# RS485.net
KiCad netlist of a schematic drawn in Altium Designer
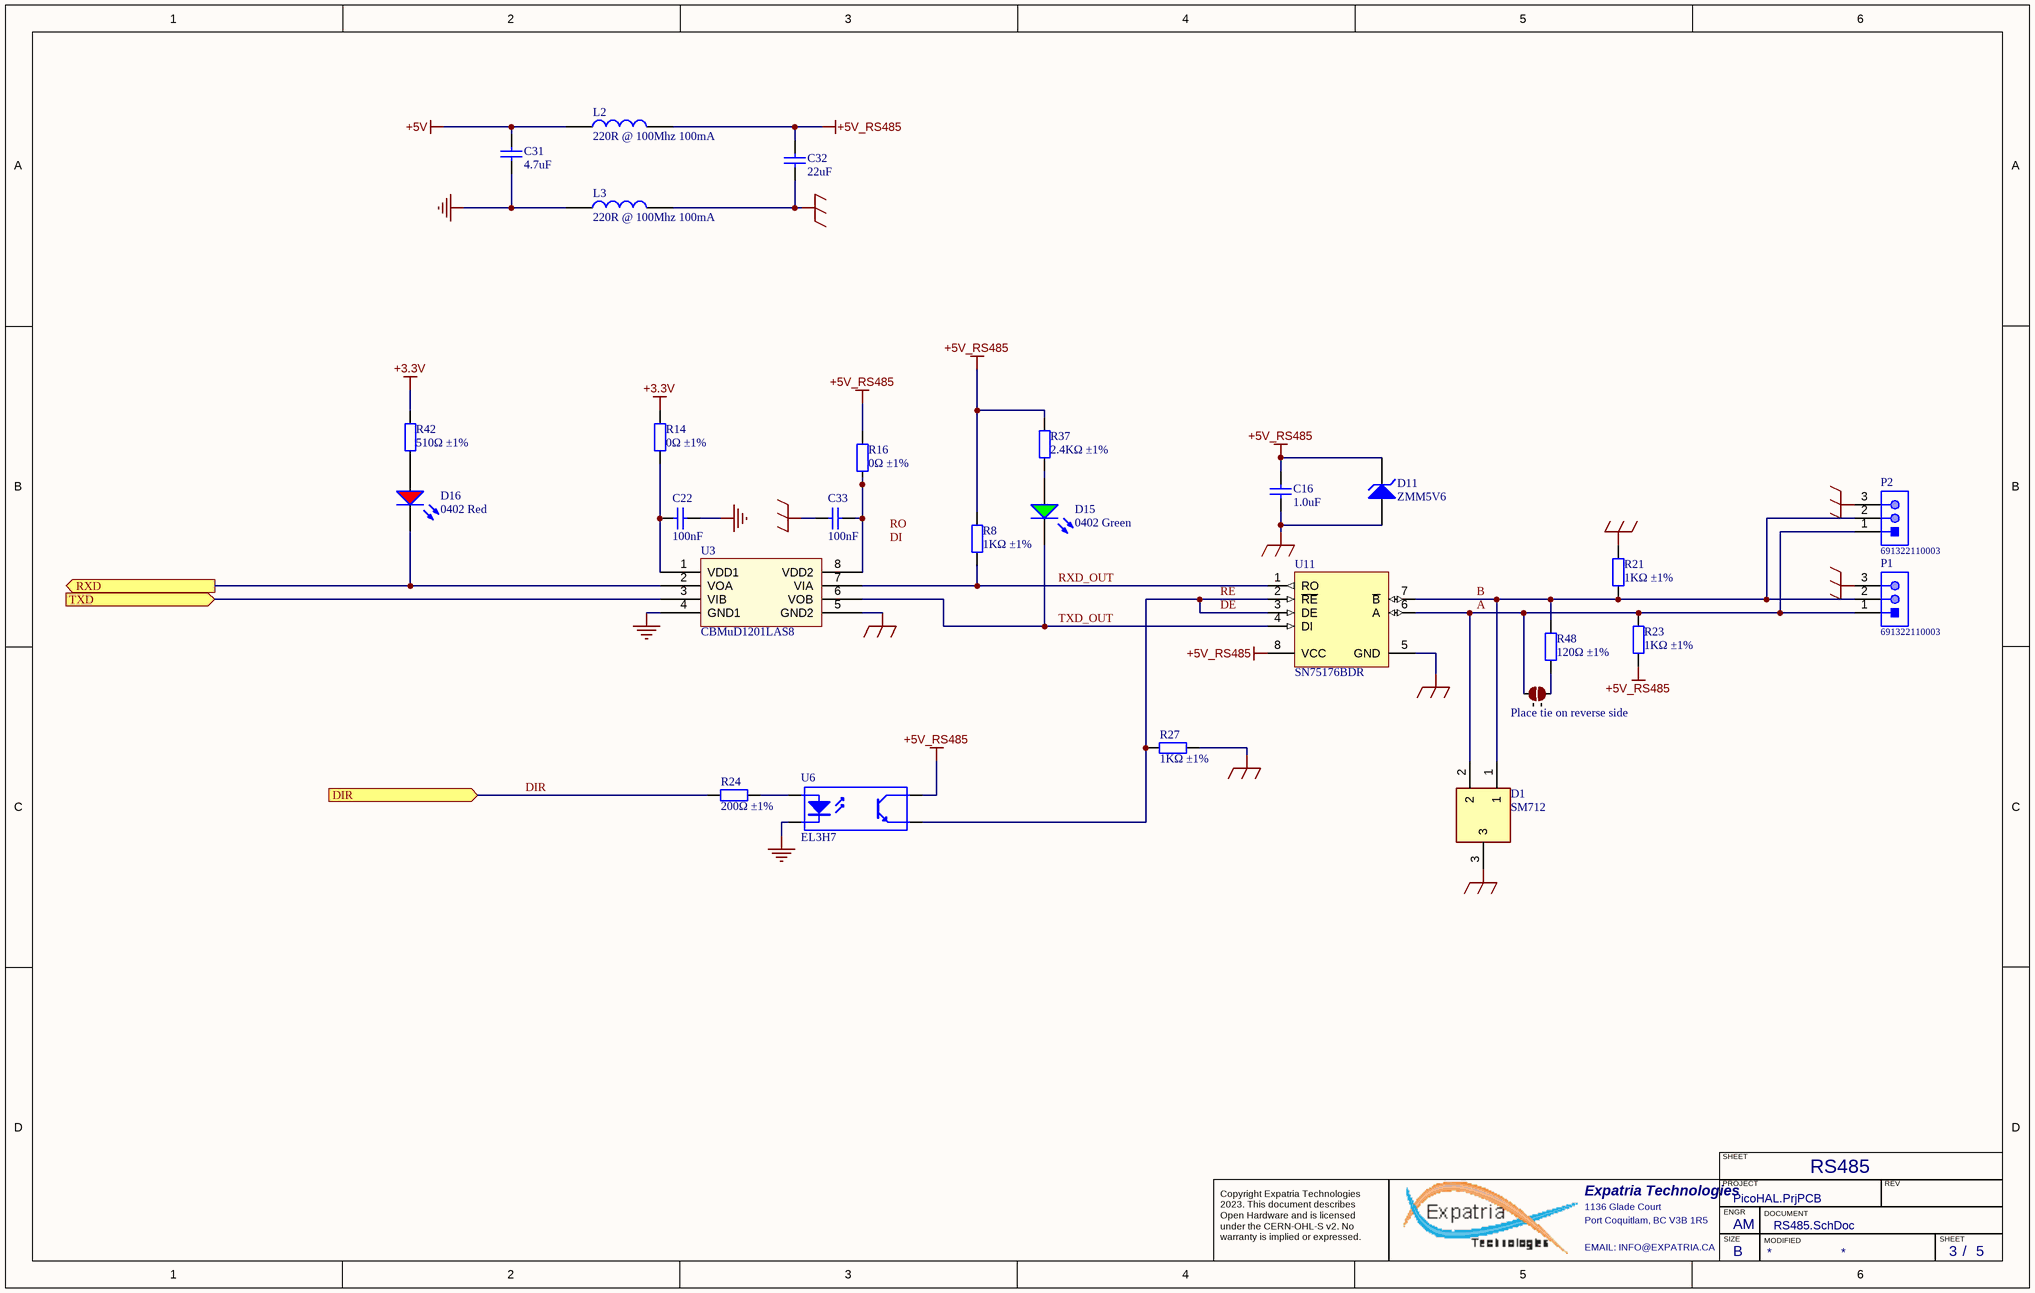
[diagram p0: RS485.SchDoc]

(export (version "E")
  (design (tool "Eeschema 10.0.6"))
  (components
    (comp (ref "C16")
      (value "1.0uF")
      (footprint "0402_C")
      (description "Chip capacitor")
      (fields
        (field (name "MANUFACTURER") "Samsung Electro-Mechanics")
        (field (name "PARTNUMBER") "CL05A105KA5NQNC")
      )
      (libsource (lib "Cap") (part "0402 1.0uF (105) 10% 25V"))
    )
    (comp (ref "C22")
      (value "100nF")
      (footprint "0402_C")
      (description "Chip capacitors")
      (fields
        (field (name "MANUFACTURER") "Samsung Electro-Mechanics")
        (field (name "PARTNUMBER") "CL05B104KO5NNNC")
      )
      (libsource (lib "Cap") (part "0402 100nF (104) 10% 16V"))
    )
    (comp (ref "C31")
      (value "4.7uF")
      (footprint "0805_C")
      (description "Chip capacitors")
      (fields
        (field (name "MANUFACTURER") "Samsung Electro-Mechanics")
        (field (name "PARTNUMBER") "CL21A475KAQNNNE")
      )
      (libsource (lib "Cap") (part "0805 4.7uF (475) 10% 25V"))
    )
    (comp (ref "C32")
      (value "22uF")
      (footprint "0805_C")
      (description "Chip capacitors")
      (fields
        (field (name "MANUFACTURER") "Samsung Electro-Mechanics")
        (field (name "PARTNUMBER") "CL21A226MAQNNNE")
      )
      (libsource (lib "Cap") (part "0805 22uF (226) 20% 25V"))
    )
    (comp (ref "C33")
      (value "100nF")
      (footprint "0402_C")
      (description "Chip capacitors")
      (fields
        (field (name "MANUFACTURER") "Samsung Electro-Mechanics")
        (field (name "PARTNUMBER") "CL05B104KO5NNNC")
      )
      (libsource (lib "Cap") (part "0402 100nF (104) 10% 16V"))
    )
    (comp (ref "D1")
      (value "SM712")
      (footprint "SamacSys:SOT95P230X117-3N")
      (description "Bidirectional 12V (Max), 7V (Max) 7.5V / 13.3V 10V / 20V 12A(8/20us) SOT-23-3 TVS RoHS")
      (libsource (lib "*") (part "CDSOT23-SM712"))
    )
    (comp (ref "D11")
      (value "ZMM5V6")
      (footprint "LL-34")
      (description "500mW - 0.1uA @ 1V 5.6V LL-34 Zener Diodes ROHS")
      (libsource (lib "Zener") (part "LL-34 ZMM5V6"))
    )
    (comp (ref "D15")
      (value "0402 Green")
      (footprint "LED 0402_1005 RED")
      (description "LED")
      (libsource (lib "LED") (part "0402 LED Green"))
    )
    (comp (ref "D16")
      (value "0402 Red")
      (footprint "LED 0402_1005 RED")
      (description "LED")
      (libsource (lib "LED") (part "0402 LED Red"))
    )
    (comp (ref "J4")
      (value "2 way net solder junction - Normally Open")
      (footprint "2waySolder_NO")
      (libsource (lib "PrintNC_GRBLHAL_Breakout") (part "2waySolderNO"))
    )
    (comp (ref "L2")
      (value "220R @ 100Mhz 100mA")
      (footprint "0402_L")
      (description "Ferrite Bead")
      (libsource (lib "FBEAD") (part "0402 220R@100Mhz 0.1A"))
    )
    (comp (ref "L3")
      (value "220R @ 100Mhz 100mA")
      (footprint "0402_L")
      (description "Ferrite Bead")
      (libsource (lib "FBEAD") (part "0402 220R@100Mhz 0.1A"))
    )
    (comp (ref "P1")
      (value "691322110003")
      (footprint "691322110003")
      (description "Serie 3221 - 3.50mm Horizontal PCB Header WR-TBL, 3 pin")
      (fields (field (name "MANUFACTURER") "Wurth Elektronik") (field (name "PUBLISHER") "WurthElektronik"))
      (libsource (lib "Altium Content Vault") (part "WE-CN-1P-M-R3"))
    )
    (comp (ref "P2")
      (value "691322110003")
      (footprint "691322110003")
      (description "Serie 3221 - 3.50mm Horizontal PCB Header WR-TBL, 3 pin")
      (libsource (lib "Altium Content Vault") (part "WE-CN-1P-M-R3"))
    )
    (comp (ref "R8")
      (value "1KΩ ±1%")
      (footprint "0402_R")
      (description "Chip resistor")
      (fields (field (name "MANUFACTURER") "Uniroyal Elec") (field (name "PARTNUMBER") "0402WGF1001TCE"))
      (libsource (lib "RES") (part "0402 1K (1001) 1%"))
    )
    (comp (ref "R14")
      (value "0Ω ±1%")
      (footprint "0402_R")
      (description "Chip resistor")
      (fields (field (name "MANUFACTURER") "Uniroyal Elec") (field (name "PARTNUMBER") "0402WGF0000TCE"))
      (libsource (lib "RES") (part "0402 0R (0R0) 1%"))
    )
    (comp (ref "R16")
      (value "0Ω ±1%")
      (footprint "0402_R")
      (description "Chip resistor")
      (fields (field (name "MANUFACTURER") "Uniroyal Elec") (field (name "PARTNUMBER") "0402WGF0000TCE"))
      (libsource (lib "RES") (part "0402 0R (0R0) 1%"))
    )
    (comp (ref "R21")
      (value "1KΩ ±1%")
      (footprint "0402_R")
      (description "Chip resistor")
      (fields (field (name "MANUFACTURER") "Uniroyal Elec") (field (name "PARTNUMBER") "0402WGF1001TCE"))
      (libsource (lib "RES") (part "0402 1K (1001) 1%"))
    )
    (comp (ref "R23")
      (value "1KΩ ±1%")
      (footprint "0402_R")
      (description "Chip resistor")
      (fields (field (name "MANUFACTURER") "Uniroyal Elec") (field (name "PARTNUMBER") "0402WGF1001TCE"))
      (libsource (lib "RES") (part "0402 1K (1001) 1%"))
    )
    (comp (ref "R24")
      (value "200Ω ±1%")
      (footprint "0402_R")
      (description "Chip resistor")
      (fields (field (name "MANUFACTURER") "Uniroyal Elec") (field (name "PARTNUMBER") "0402WGF2000TCE"))
      (libsource (lib "RES") (part "0402 200R (2000) 1%"))
    )
    (comp (ref "R27")
      (value "1KΩ ±1%")
      (footprint "0402_R")
      (description "Chip resistor")
      (fields (field (name "MANUFACTURER") "Uniroyal Elec") (field (name "PARTNUMBER") "0402WGF1001TCE"))
      (libsource (lib "") (part "0402 1K (1001) 1%_1"))
    )
    (comp (ref "R37")
      (value "2.4KΩ ±1%")
      (footprint "0402_R")
      (description "Chip resistor")
      (fields (field (name "MANUFACTURER") "Uniroyal Elec") (field (name "PARTNUMBER") "0402WGF2401TCE"))
      (libsource (lib "RES") (part "0402 2.4K (2401) 1%"))
    )
    (comp (ref "R42")
      (value "510Ω ±1%")
      (footprint "0402_R")
      (description "Chip resistor")
      (fields (field (name "MANUFACTURER") "Uniroyal Elec") (field (name "PARTNUMBER") "0402WGF5100TCE"))
      (libsource (lib "PrintNC_GRBLHAL_Breakout") (part "0402 510R (5100) 1%"))
    )
    (comp (ref "R48")
      (value "120Ω ±1%")
      (footprint "0805_R")
      (description "Chip resistor")
      (fields (field (name "MANUFACTURER") "Uniroyal Elec") (field (name "POWER") "1/8W"))
      (libsource (lib "RES") (part "0805 120R (1200) 1%"))
    )
    (comp (ref "U3")
      (value "CBMuD1201LAS8")
      (footprint "SOIC-8_150mil")
      (description "Dual Channel Isolator")
      (libsource (lib "IC") (part "CBMuD1201LAS8"))
    )
    (comp (ref "U6")
      (value "EL3H7")
      (footprint "SOIC127P700X200-4N")
      (libsource (lib "IC") (part "EL3H7(C)(TA)-G_[C92243]"))
    )
    (comp (ref "U11")
      (value "SN75176BDR")
      (footprint "Miscellaneous Devices LC:SOIC-8_150mil")
      (description "RS-485/RS-422")
      (libsource (lib "IC") (part "SN75176BDR_[C7063]"))
    )
  )
  (nets
    (net (code "1") (name "+3.3V") (class "Default")
      (node (ref "R14") (pin "2") (pinfunction "2_2") (pintype "passive"))
      (node (ref "R42") (pin "1") (pinfunction "1_1") (pintype "passive"))
    )
    (net (code "2") (name "+5V") (class "Default")
      (node (ref "C31") (pin "2") (pinfunction "2_2") (pintype "passive"))
      (node (ref "L2") (pin "1") (pinfunction "1_1") (pintype "passive"))
    )
    (net (code "3") (name "+5V_RS485") (class "Default")
      (node (ref "C16") (pin "2") (pinfunction "2_2") (pintype "passive"))
      (node (ref "C32") (pin "2") (pinfunction "2_2") (pintype "passive"))
      (node (ref "D11") (pin "2") (pinfunction "K_2") (pintype "passive"))
      (node (ref "L2") (pin "2") (pinfunction "2_2") (pintype "passive"))
      (node (ref "R16") (pin "2") (pinfunction "2_2") (pintype "passive"))
      (node (ref "R23") (pin "1") (pinfunction "1_1") (pintype "passive"))
      (node (ref "R37") (pin "2") (pinfunction "2_2") (pintype "passive"))
      (node (ref "R8") (pin "2") (pinfunction "2_2") (pintype "passive"))
      (node (ref "U11") (pin "8") (pinfunction "VCC_8") (pintype "power_in"))
      (node (ref "U6") (pin "4") (pinfunction "C_4") (pintype "passive"))
    )
    (net (code "4") (name "/A") (class "Default")
      (node (ref "D1") (pin "2") (pinfunction "2_2") (pintype "passive"))
      (node (ref "J4") (pin "1") (pinfunction "1_1") (pintype "passive"))
      (node (ref "P1") (pin "1") (pinfunction "1_1") (pintype "passive"))
      (node (ref "P2") (pin "1") (pinfunction "1_1") (pintype "passive"))
      (node (ref "R23") (pin "2") (pinfunction "2_2") (pintype "passive"))
      (node (ref "U11") (pin "6") (pinfunction "A_6") (pintype "bidirectional"))
    )
    (net (code "5") (name "/B") (class "Default")
      (node (ref "D1") (pin "1") (pinfunction "1_1") (pintype "passive"))
      (node (ref "P1") (pin "2") (pinfunction "2_2") (pintype "passive"))
      (node (ref "P2") (pin "2") (pinfunction "2_2") (pintype "passive"))
      (node (ref "R21") (pin "1") (pinfunction "1_1") (pintype "passive"))
      (node (ref "R48") (pin "2") (pinfunction "2_2") (pintype "passive"))
      (node (ref "U11") (pin "7") (pinfunction "~{B}_7") (pintype "bidirectional"))
    )
    (net (code "6") (name "/DE") (class "Default")
      (node (ref "R27") (pin "1") (pinfunction "1_1") (pintype "passive"))
      (node (ref "U11") (pin "2") (pinfunction "~{RE}_2") (pintype "input"))
      (node (ref "U11") (pin "3") (pinfunction "DE_3") (pintype "input"))
      (node (ref "U6") (pin "3") (pinfunction "E_3") (pintype "passive"))
    )
    (net (code "8") (name "/DIR") (class "Default")
      (node (ref "R24") (pin "2") (pinfunction "2_2") (pintype "passive"))
    )
    (net (code "10") (name "/RXD") (class "Default")
      (node (ref "D16") (pin "K") (pinfunction "K_K") (pintype "passive"))
      (node (ref "U3") (pin "2") (pinfunction "VOA_2") (pintype "passive"))
    )
    (net (code "11") (name "/RXD_OUT") (class "Default")
      (node (ref "R8") (pin "1") (pinfunction "1_1") (pintype "passive"))
      (node (ref "U11") (pin "1") (pinfunction "RO_1") (pintype "output"))
      (node (ref "U3") (pin "7") (pinfunction "VIA_7") (pintype "passive"))
    )
    (net (code "12") (name "/TXD") (class "Default")
      (node (ref "U3") (pin "3") (pinfunction "VIB_3") (pintype "passive"))
    )
    (net (code "13") (name "/TXD_OUT") (class "Default")
      (node (ref "D15") (pin "K") (pinfunction "K_K") (pintype "passive"))
      (node (ref "U11") (pin "4") (pinfunction "DI_4") (pintype "input"))
      (node (ref "U3") (pin "6") (pinfunction "VOB_6") (pintype "passive"))
    )
    (net (code "14") (name "GND") (class "Default")
      (node (ref "C22") (pin "2") (pinfunction "2_2") (pintype "passive"))
      (node (ref "C31") (pin "1") (pinfunction "1_1") (pintype "passive"))
      (node (ref "L3") (pin "1") (pinfunction "1_1") (pintype "passive"))
      (node (ref "U3") (pin "4") (pinfunction "GND1_4") (pintype "passive"))
      (node (ref "U6") (pin "2") (pinfunction "K_2") (pintype "passive"))
    )
    (net (code "15") (name "MOD_GND") (class "Default")
      (node (ref "C16") (pin "1") (pinfunction "1_1") (pintype "passive"))
      (node (ref "C32") (pin "1") (pinfunction "1_1") (pintype "passive"))
      (node (ref "C33") (pin "1") (pinfunction "1_1") (pintype "passive"))
      (node (ref "D1") (pin "3") (pinfunction "3_3") (pintype "passive"))
      (node (ref "D11") (pin "1") (pinfunction "A_1") (pintype "passive"))
      (node (ref "L3") (pin "2") (pinfunction "2_2") (pintype "passive"))
      (node (ref "P1") (pin "3") (pinfunction "3_3") (pintype "passive"))
      (node (ref "P2") (pin "3") (pinfunction "3_3") (pintype "passive"))
      (node (ref "R21") (pin "2") (pinfunction "2_2") (pintype "passive"))
      (node (ref "R27") (pin "2") (pinfunction "2_2") (pintype "passive"))
      (node (ref "U11") (pin "5") (pinfunction "GND_5") (pintype "power_in"))
      (node (ref "U3") (pin "5") (pinfunction "GND2_5") (pintype "passive"))
    )
    (net (code "16") (name "Net-(D15-PadA)") (class "Default")
      (node (ref "D15") (pin "A") (pinfunction "A_A") (pintype "passive"))
      (node (ref "R37") (pin "1") (pinfunction "1_1") (pintype "passive"))
    )
    (net (code "17") (name "Net-(D16-PadA)") (class "Default")
      (node (ref "D16") (pin "A") (pinfunction "A_A") (pintype "passive"))
      (node (ref "R42") (pin "2") (pinfunction "2_2") (pintype "passive"))
    )
    (net (code "18") (name "Net-(J4-Pad2)") (class "Default")
      (node (ref "J4") (pin "2") (pinfunction "2_2") (pintype "passive"))
      (node (ref "R48") (pin "1") (pinfunction "1_1") (pintype "passive"))
    )
    (net (code "19") (name "Net-(U3-VDD1)") (class "Default")
      (node (ref "C22") (pin "1") (pinfunction "1_1") (pintype "passive"))
      (node (ref "R14") (pin "1") (pinfunction "1_1") (pintype "passive"))
      (node (ref "U3") (pin "1") (pinfunction "VDD1_1") (pintype "passive"))
    )
    (net (code "20") (name "Net-(U3-VDD2)") (class "Default")
      (node (ref "C33") (pin "2") (pinfunction "2_2") (pintype "passive"))
      (node (ref "R16") (pin "1") (pinfunction "1_1") (pintype "passive"))
      (node (ref "U3") (pin "8") (pinfunction "VDD2_8") (pintype "passive"))
    )
    (net (code "21") (name "Net-(U6-A)") (class "Default")
      (node (ref "R24") (pin "1") (pinfunction "1_1") (pintype "passive"))
      (node (ref "U6") (pin "1") (pinfunction "A_1") (pintype "passive"))
    )
  )
)
